# Supply_DAC.net
KiCad netlist of a schematic drawn in Altium Designer
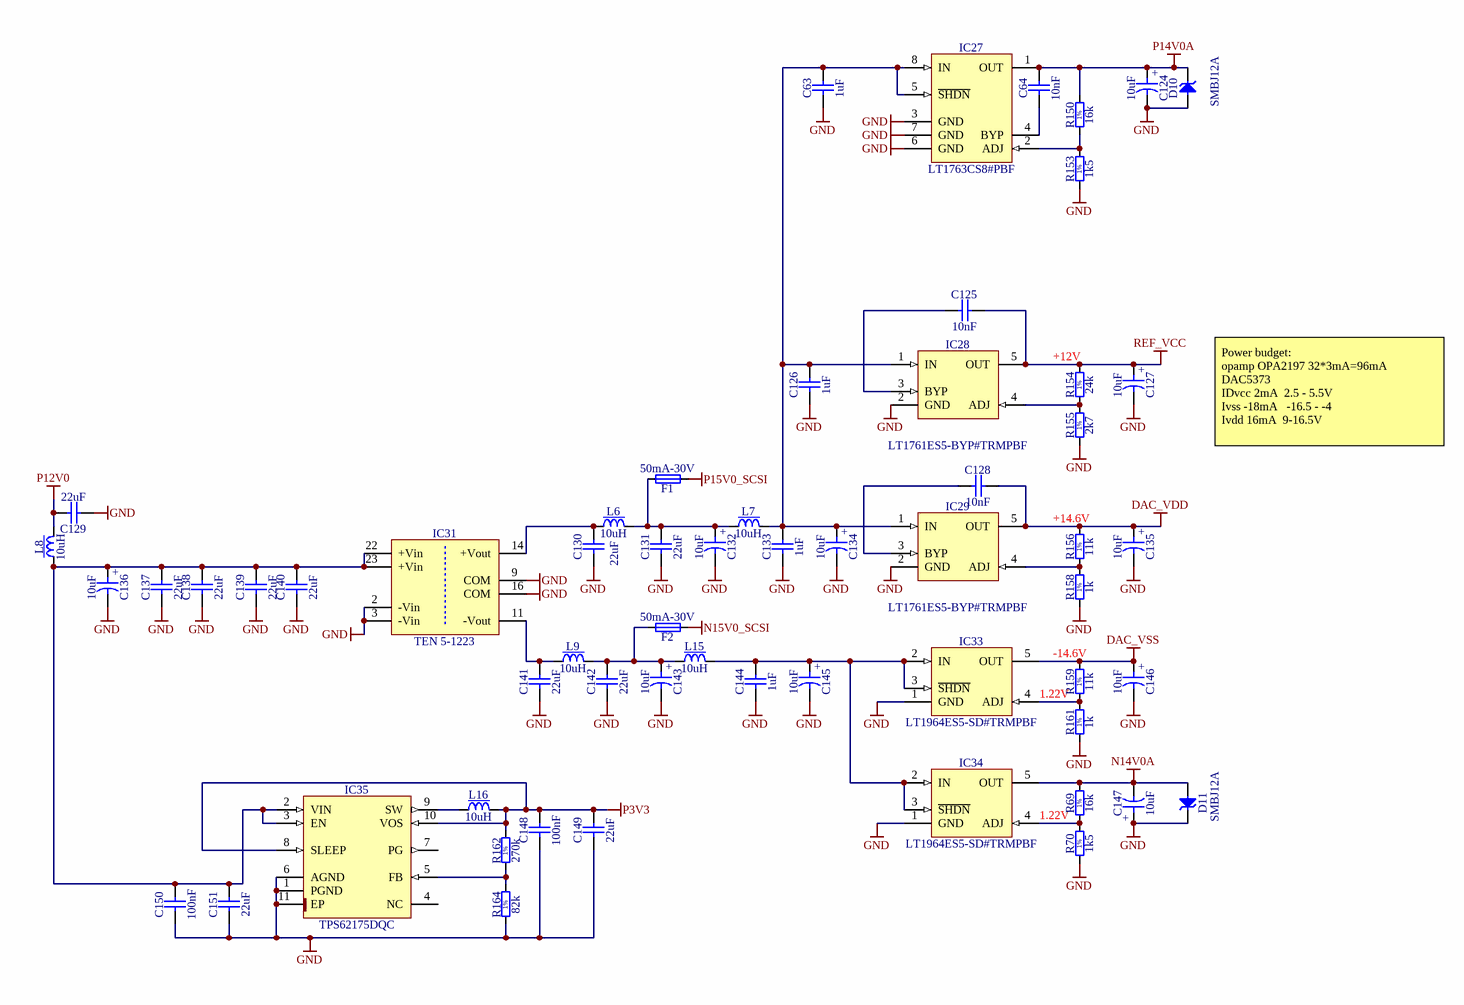
[diagram p0: Supply_DAC.SchDoc]

(export (version "E")
  (design (tool "Eeschema 10.0.6"))
  (components
    (comp (ref "C63")
      (value "1uF")
      (footprint "CAPC1608X87N")
      (description "Non-polarised capacitor")
      (fields
        (field (name "PART NUMBER") "CC0603_1UF_25V_10%_X7R")
        (field (name "VOLTAGE") "25V")
        (field (name "AUTHOR") "CERN DEM JLC")
      )
      (libsource (lib "Capacitors") (part "Capacitor - non polarized"))
    )
    (comp (ref "C64")
      (value "10nF")
      (footprint "CAPC1608X87N")
      (description "Non-polarised capacitor")
      (fields
        (field (name "PART NUMBER") "CC0603_10NF_50V_10%_X7R")
        (field (name "VOLTAGE") "50V")
        (field (name "AUTHOR") "CERN DEM JLC")
      )
      (libsource (lib "Capacitors") (part "Capacitor - non polarized"))
    )
    (comp (ref "C124")
      (value "10uF")
      (footprint "CAPMP3216X180N")
      (description "Polarised capacitor")
      (fields
        (field (name "PART NUMBER") "CTE3216-18_10UF_16V_20%_AVX_TCJ")
        (field (name "VOLTAGE") "16V")
        (field (name "AUTHOR") "CERN DEM JLC")
      )
      (libsource (lib "Capacitors") (part "Capacitor - polarized"))
    )
    (comp (ref "C125")
      (value "10nF")
      (footprint "CAPC1608X87N")
      (description "Non-polarised capacitor")
      (fields
        (field (name "PART NUMBER") "CC0603_10NF_50V_10%_X7R")
        (field (name "VOLTAGE") "50V")
        (field (name "AUTHOR") "CERN DEM JLC")
      )
      (libsource (lib "Capacitors") (part "Capacitor - non polarized"))
    )
    (comp (ref "C126")
      (value "1uF")
      (footprint "CAPC1608X87N")
      (description "Non-polarised capacitor")
      (fields
        (field (name "PART NUMBER") "CC0603_1UF_25V_10%_X7R")
        (field (name "VOLTAGE") "25V")
        (field (name "AUTHOR") "CERN DEM JLC")
      )
      (libsource (lib "Capacitors") (part "Capacitor - non polarized"))
    )
    (comp (ref "C127")
      (value "10uF")
      (footprint "CAPMP3216X180N")
      (description "Polarised capacitor")
      (fields
        (field (name "PART NUMBER") "CTE3216-18_10UF_16V_20%_AVX_TCJ")
        (field (name "VOLTAGE") "16V")
        (field (name "AUTHOR") "CERN DEM JLC")
      )
      (libsource (lib "Capacitors") (part "Capacitor - polarized"))
    )
    (comp (ref "C128")
      (value "10nF")
      (footprint "CAPC1608X87N")
      (description "Non-polarised capacitor")
      (fields
        (field (name "PART NUMBER") "CC0603_10NF_50V_10%_X7R")
        (field (name "VOLTAGE") "50V")
        (field (name "AUTHOR") "CERN DEM JLC")
      )
      (libsource (lib "Capacitors") (part "Capacitor - non polarized"))
    )
    (comp (ref "C129")
      (value "22uF")
      (footprint "CAPC2012X135N")
      (description "Non-polarised capacitor")
      (fields
        (field (name "PART NUMBER") "CC0805_22UF_16V_10%_X5R")
        (field (name "VOLTAGE") "16V")
        (field (name "AUTHOR") "CERN DEM JLC")
      )
      (libsource (lib "Capacitors") (part "Capacitor - non polarized"))
    )
    (comp (ref "C130")
      (value "22uF")
      (footprint "CAPC2012X135N")
      (description "Non-polarised capacitor")
      (fields
        (field (name "PART NUMBER") "CC0805_22UF_16V_10%_X5R")
        (field (name "VOLTAGE") "16V")
        (field (name "AUTHOR") "CERN DEM JLC")
      )
      (libsource (lib "Capacitors") (part "Capacitor - non polarized"))
    )
    (comp (ref "C131")
      (value "22uF")
      (footprint "CAPC2012X135N")
      (description "Non-polarised capacitor")
      (fields
        (field (name "PART NUMBER") "CC0805_22UF_16V_10%_X5R")
        (field (name "VOLTAGE") "16V")
        (field (name "AUTHOR") "CERN DEM JLC")
      )
      (libsource (lib "Capacitors") (part "Capacitor - non polarized"))
    )
    (comp (ref "C132")
      (value "10uF")
      (footprint "CAPMP3216X180N")
      (description "Polarised capacitor")
      (fields
        (field (name "PART NUMBER") "CTE3216-18_10UF_16V_20%_AVX_TCJ")
        (field (name "VOLTAGE") "16V")
        (field (name "AUTHOR") "CERN DEM JLC")
      )
      (libsource (lib "Capacitors") (part "Capacitor - polarized"))
    )
    (comp (ref "C133")
      (value "1uF")
      (footprint "CAPC1608X87N")
      (description "Non-polarised capacitor")
      (fields
        (field (name "PART NUMBER") "CC0603_1UF_25V_10%_X7R")
        (field (name "VOLTAGE") "25V")
        (field (name "AUTHOR") "CERN DEM JLC")
      )
      (libsource (lib "Capacitors") (part "Capacitor - non polarized"))
    )
    (comp (ref "C134")
      (value "10uF")
      (footprint "CAPMP3216X180N")
      (description "Polarised capacitor")
      (fields
        (field (name "PART NUMBER") "CTE3216-18_10UF_16V_20%_AVX_TCJ")
        (field (name "VOLTAGE") "16V")
        (field (name "AUTHOR") "CERN DEM JLC")
      )
      (libsource (lib "Capacitors") (part "Capacitor - polarized"))
    )
    (comp (ref "C135")
      (value "10uF")
      (footprint "CAPMP3216X180N")
      (description "Polarised capacitor")
      (fields
        (field (name "PART NUMBER") "CTE3216-18_10UF_16V_20%_AVX_TCJ")
        (field (name "VOLTAGE") "16V")
        (field (name "AUTHOR") "CERN DEM JLC")
      )
      (libsource (lib "Capacitors") (part "Capacitor - polarized"))
    )
    (comp (ref "C136")
      (value "10uF")
      (footprint "CAPMP3216X180N")
      (description "Polarised capacitor")
      (fields
        (field (name "PART NUMBER") "CTE3216-18_10UF_16V_20%_AVX_TCJ")
        (field (name "VOLTAGE") "16V")
        (field (name "AUTHOR") "CERN DEM JLC")
      )
      (libsource (lib "Capacitors") (part "Capacitor - polarized"))
    )
    (comp (ref "C137")
      (value "22uF")
      (footprint "CAPC2012X135N")
      (description "Non-polarised capacitor")
      (fields
        (field (name "PART NUMBER") "CC0805_22UF_16V_10%_X5R")
        (field (name "VOLTAGE") "16V")
        (field (name "AUTHOR") "CERN DEM JLC")
      )
      (libsource (lib "Capacitors") (part "Capacitor - non polarized"))
    )
    (comp (ref "C138")
      (value "22uF")
      (footprint "CAPC2012X135N")
      (description "Non-polarised capacitor")
      (fields
        (field (name "PART NUMBER") "CC0805_22UF_16V_10%_X5R")
        (field (name "VOLTAGE") "16V")
        (field (name "AUTHOR") "CERN DEM JLC")
      )
      (libsource (lib "Capacitors") (part "Capacitor - non polarized"))
    )
    (comp (ref "C139")
      (value "22uF")
      (footprint "CAPC2012X135N")
      (description "Non-polarised capacitor")
      (fields
        (field (name "PART NUMBER") "CC0805_22UF_16V_10%_X5R")
        (field (name "VOLTAGE") "16V")
        (field (name "AUTHOR") "CERN DEM JLC")
      )
      (libsource (lib "Capacitors") (part "Capacitor - non polarized"))
    )
    (comp (ref "C140")
      (value "22uF")
      (footprint "CAPC2012X135N")
      (description "Non-polarised capacitor")
      (fields
        (field (name "PART NUMBER") "CC0805_22UF_16V_10%_X5R")
        (field (name "VOLTAGE") "16V")
        (field (name "AUTHOR") "CERN DEM JLC")
      )
      (libsource (lib "Capacitors") (part "Capacitor - non polarized"))
    )
    (comp (ref "C141")
      (value "22uF")
      (footprint "CAPC2012X135N")
      (description "Non-polarised capacitor")
      (fields
        (field (name "PART NUMBER") "CC0805_22UF_16V_10%_X5R")
        (field (name "VOLTAGE") "16V")
        (field (name "AUTHOR") "CERN DEM JLC")
      )
      (libsource (lib "Capacitors") (part "Capacitor - non polarized"))
    )
    (comp (ref "C142")
      (value "22uF")
      (footprint "CAPC2012X135N")
      (description "Non-polarised capacitor")
      (fields
        (field (name "PART NUMBER") "CC0805_22UF_16V_10%_X5R")
        (field (name "VOLTAGE") "16V")
        (field (name "AUTHOR") "CERN DEM JLC")
      )
      (libsource (lib "Capacitors") (part "Capacitor - non polarized"))
    )
    (comp (ref "C143")
      (value "10uF")
      (footprint "CAPMP3216X180N")
      (description "Polarised capacitor")
      (fields
        (field (name "PART NUMBER") "CTE3216-18_10UF_16V_20%_AVX_TCJ")
        (field (name "VOLTAGE") "16V")
        (field (name "AUTHOR") "CERN DEM JLC")
      )
      (libsource (lib "Capacitors") (part "Capacitor - polarized"))
    )
    (comp (ref "C144")
      (value "1uF")
      (footprint "CAPC1608X87N")
      (description "Non-polarised capacitor")
      (fields
        (field (name "PART NUMBER") "CC0603_1UF_25V_10%_X7R")
        (field (name "VOLTAGE") "25V")
        (field (name "AUTHOR") "CERN DEM JLC")
      )
      (libsource (lib "Capacitors") (part "Capacitor - non polarized"))
    )
    (comp (ref "C145")
      (value "10uF")
      (footprint "CAPMP3216X180N")
      (description "Polarised capacitor")
      (fields
        (field (name "PART NUMBER") "CTE3216-18_10UF_16V_20%_AVX_TCJ")
        (field (name "VOLTAGE") "16V")
        (field (name "AUTHOR") "CERN DEM JLC")
      )
      (libsource (lib "Capacitors") (part "Capacitor - polarized"))
    )
    (comp (ref "C146")
      (value "10uF")
      (footprint "CAPMP3216X180N")
      (description "Polarised capacitor")
      (fields
        (field (name "PART NUMBER") "CTE3216-18_10UF_16V_20%_AVX_TCJ")
        (field (name "VOLTAGE") "16V")
        (field (name "AUTHOR") "CERN DEM JLC")
      )
      (libsource (lib "Capacitors") (part "Capacitor - polarized"))
    )
    (comp (ref "C147")
      (value "10uF")
      (footprint "CAPMP3216X180N")
      (description "Polarised capacitor")
      (fields
        (field (name "PART NUMBER") "CTE3216-18_10UF_16V_20%_AVX_TCJ")
        (field (name "VOLTAGE") "16V")
        (field (name "AUTHOR") "CERN DEM JLC")
      )
      (libsource (lib "Capacitors") (part "Capacitor - polarized"))
    )
    (comp (ref "C148")
      (value "100nF")
      (footprint "CAPC1005X55N")
      (description "Non-polarised capacitor")
      (fields
        (field (name "PART NUMBER") "CC0402_100NF_16V_10%_X5R")
        (field (name "VOLTAGE") "16V")
        (field (name "AUTHOR") "CERN DEM JLC")
      )
      (libsource (lib "Capacitors") (part "Capacitor - non polarized"))
    )
    (comp (ref "C149")
      (value "22uF")
      (footprint "CAPC2012X135N")
      (description "Non-polarised capacitor")
      (fields
        (field (name "PART NUMBER") "CC0805_22UF_16V_10%_X5R")
        (field (name "VOLTAGE") "16V")
        (field (name "AUTHOR") "CERN DEM JLC")
      )
      (libsource (lib "Capacitors") (part "Capacitor - non polarized"))
    )
    (comp (ref "C150")
      (value "100nF")
      (footprint "CAPC1005X55N")
      (description "Non-polarised capacitor")
      (fields
        (field (name "PART NUMBER") "CC0402_100NF_16V_10%_X5R")
        (field (name "VOLTAGE") "16V")
        (field (name "AUTHOR") "CERN DEM JLC")
      )
      (libsource (lib "Capacitors") (part "Capacitor - non polarized"))
    )
    (comp (ref "C151")
      (value "22uF")
      (footprint "CAPC2012X135N")
      (description "Non-polarised capacitor")
      (fields
        (field (name "PART NUMBER") "CC0805_22UF_16V_10%_X5R")
        (field (name "VOLTAGE") "16V")
        (field (name "AUTHOR") "CERN DEM JLC")
      )
      (libsource (lib "Capacitors") (part "Capacitor - non polarized"))
    )
    (comp (ref "D10")
      (value "SMBJ12A")
      (footprint "DIOM5336X265N")
      (description "Zener Diode")
      (fields
        (field (name "VOLTAGE") "12V")
        (field (name "POWER") "600W")
        (field (name "AUTHOR") "CERN DEM JLC")
      )
      (libsource (lib "ICs And Semiconductors") (part "Diode Zener"))
    )
    (comp (ref "D11")
      (value "SMBJ12A")
      (footprint "DIOM5336X265N")
      (description "Zener Diode")
      (fields
        (field (name "VOLTAGE") "12V")
        (field (name "POWER") "600W")
        (field (name "AUTHOR") "CERN DEM JLC")
      )
      (libsource (lib "ICs And Semiconductors") (part "Diode Zener"))
    )
    (comp (ref "F1")
      (value "50mA-30V")
      (footprint "FUSRC3226X85N")
      (description "Fuse")
      (fields
        (field (name "PART NUMBER") "FUSR1210_TYCO-MICROSMD005F")
        (field (name "MANUFACTURER") "TYCO ELECTRONICS")
        (field (name "AUTHOR") "CERN DEM JLC")
      )
      (libsource (lib "Eletro-mechanical") (part "Fuse"))
    )
    (comp (ref "F2")
      (value "50mA-30V")
      (footprint "FUSRC3226X85N")
      (description "Fuse")
      (fields
        (field (name "PART NUMBER") "FUSR1210_TYCO-MICROSMD005F")
        (field (name "MANUFACTURER") "TYCO ELECTRONICS")
        (field (name "AUTHOR") "CERN DEM JLC")
      )
      (libsource (lib "Eletro-mechanical") (part "Fuse"))
    )
    (comp (ref "IC27")
      (value "LT1763CS8#PBF")
      (footprint "SOIC127P600X175-8N")
      (description "1.22V to 20V 500mA, Low Noise, LDO Adjustable Micropower Regulator")
      (fields (field (name "MANUFACTURER") "LINEAR TECHNOLOGY") (field (name "AUTHOR") "CERN DEM JLC"))
      (libsource (lib "ICs And Semiconductors") (part "LT1763xS8"))
    )
    (comp (ref "IC28")
      (value "LT1761ES5-BYP#TRMPBF")
      (footprint "SOT95P280X100-5N")
      (description "100mA, Low Noise, LDO Micropower Adjustable Regulator in SOT-23")
      (fields (field (name "MANUFACTURER") "LINEAR TECHNOLOGY") (field (name "AUTHOR") "CERN DEM MR"))
      (libsource (lib "ICs And Semiconductors") (part "LT1761-BYP"))
    )
    (comp (ref "IC29")
      (value "LT1761ES5-BYP#TRMPBF")
      (footprint "SOT95P280X100-5N")
      (description "100mA, Low Noise, LDO Micropower Adjustable Regulator in SOT-23")
      (fields (field (name "MANUFACTURER") "LINEAR TECHNOLOGY") (field (name "AUTHOR") "CERN DEM MR"))
      (libsource (lib "ICs And Semiconductors") (part "LT1761-BYP"))
    )
    (comp (ref "IC31")
      (value "TEN 5-1223")
      (footprint "DCDC_TRACO_TEN5WI")
      (description "9-18V to ±15V, Iout (max) ±200mA, 6W DC-DC Converter")
      (fields (field (name "MANUFACTURER") "TRACO POWER") (field (name "AUTHOR") "GK"))
      (libsource (lib "LIBRARY_SCH") (part "DCDC_TRACO_TEN 5-1223"))
    )
    (comp (ref "IC33")
      (value "LT1964ES5-SD#TRMPBF")
      (footprint "SOT95P280X100-5N")
      (description "200mA, Low Noise, Low Dropout Negative Micropower Regulator")
      (fields (field (name "MANUFACTURER") "LINEAR TECHNOLOGY") (field (name "AUTHOR") "CERN DEM JLC"))
      (libsource (lib "ICs And Semiconductors") (part "LT1964-SD"))
    )
    (comp (ref "IC34")
      (value "LT1964ES5-SD#TRMPBF")
      (footprint "SOT95P280X100-5N")
      (description "200mA, Low Noise, Low Dropout Negative Micropower Regulator")
      (fields (field (name "MANUFACTURER") "LINEAR TECHNOLOGY") (field (name "AUTHOR") "CERN DEM JLC"))
      (libsource (lib "ICs And Semiconductors") (part "LT1964-SD"))
    )
    (comp (ref "IC35")
      (value "TPS62175DQC")
      (footprint "SON50P200X300X80-11N-R94X250")
      (description "4.75-28VDC to 1-6VDC, 500mA Step-Down Converter With Sleep Mode")
      (fields (field (name "MANUFACTURER") "TEXAS INSTRUMENTS") (field (name "AUTHOR") "CERN DEM JMW"))
      (libsource (lib "ICs And Semiconductors") (part "TPS62175"))
    )
    (comp (ref "L6")
      (value "10uH")
      (footprint "IND_MURATA-PS_8400")
      (description "Inductor With Core")
      (fields
        (field (name "PART NUMBER") "IND_10UH_10%_MURATA-PS_8400")
        (field (name "POWER") "950mA")
        (field (name "AUTHOR") "CERN DEM JLC")
      )
      (libsource (lib "Inductors & Transformers") (part "Inductor With Magnetic core"))
    )
    (comp (ref "L7")
      (value "10uH")
      (footprint "IND_MURATA-PS_8400")
      (description "Inductor With Core")
      (fields
        (field (name "PART NUMBER") "IND_10UH_10%_MURATA-PS_8400")
        (field (name "POWER") "950mA")
        (field (name "AUTHOR") "CERN DEM JLC")
      )
      (libsource (lib "Inductors & Transformers") (part "Inductor With Magnetic core"))
    )
    (comp (ref "L8")
      (value "10uH")
      (footprint "IND_MURATA-PS_8400")
      (description "Inductor With Core")
      (fields
        (field (name "PART NUMBER") "IND_10UH_10%_MURATA-PS_8400")
        (field (name "POWER") "950mA")
        (field (name "AUTHOR") "CERN DEM JLC")
      )
      (libsource (lib "") (part "Inductor With Magnetic core_1"))
    )
    (comp (ref "L9")
      (value "10uH")
      (footprint "IND_MURATA-PS_8400")
      (description "Inductor With Core")
      (fields
        (field (name "PART NUMBER") "IND_10UH_10%_MURATA-PS_8400")
        (field (name "POWER") "950mA")
        (field (name "AUTHOR") "CERN DEM JLC")
      )
      (libsource (lib "Inductors & Transformers") (part "Inductor With Magnetic core"))
    )
    (comp (ref "L15")
      (value "10uH")
      (footprint "IND_MURATA-PS_8400")
      (description "Inductor With Core")
      (fields
        (field (name "PART NUMBER") "IND_10UH_10%_MURATA-PS_8400")
        (field (name "POWER") "950mA")
        (field (name "AUTHOR") "CERN DEM JLC")
      )
      (libsource (lib "Inductors & Transformers") (part "Inductor With Magnetic core"))
    )
    (comp (ref "L16")
      (value "10uH")
      (footprint "IND_MURATA-PS_8400")
      (description "Inductor With Core")
      (fields
        (field (name "PART NUMBER") "IND_10UH_10%_MURATA-PS_8400")
        (field (name "POWER") "950mA")
        (field (name "AUTHOR") "CERN DEM JLC")
      )
      (libsource (lib "Inductors & Transformers") (part "Inductor With Magnetic core"))
    )
    (comp (ref "R69")
      (value "16k")
      (footprint "RESC1608X55N")
      (description "Resistor - 1%")
      (fields
        (field (name "PART NUMBER") "R0603_16K_1%_0.1W_100PPM")
        (field (name "POWER") "0.1W")
        (field (name "AUTHOR") "CERN DEM JLC")
      )
      (libsource (lib "Resistors") (part "Resistor - 1%"))
    )
    (comp (ref "R70")
      (value "1k5")
      (footprint "RESC1608X55N")
      (description "Resistor - 1%")
      (fields
        (field (name "PART NUMBER") "R0603_1K5_1%_0.1W_100PPM")
        (field (name "POWER") "0.1W")
        (field (name "AUTHOR") "CERN DEM JLC")
      )
      (libsource (lib "Resistors") (part "Resistor - 1%"))
    )
    (comp (ref "R150")
      (value "16k")
      (footprint "RESC1608X55N")
      (description "Resistor - 1%")
      (fields
        (field (name "PART NUMBER") "R0603_16K_1%_0.1W_100PPM")
        (field (name "POWER") "0.1W")
        (field (name "AUTHOR") "CERN DEM JLC")
      )
      (libsource (lib "Resistors") (part "Resistor - 1%"))
    )
    (comp (ref "R153")
      (value "1k5")
      (footprint "RESC1608X55N")
      (description "Resistor - 1%")
      (fields
        (field (name "PART NUMBER") "R0603_1K5_1%_0.1W_100PPM")
        (field (name "POWER") "0.1W")
        (field (name "AUTHOR") "CERN DEM JLC")
      )
      (libsource (lib "Resistors") (part "Resistor - 1%"))
    )
    (comp (ref "R154")
      (value "24k")
      (footprint "RESC1608X55N")
      (description "Resistor - 1%")
      (fields
        (field (name "PART NUMBER") "R0603_24K_1%_0.1W_100PPM")
        (field (name "POWER") "0.1W")
        (field (name "AUTHOR") "CERN DEM JLC")
      )
      (libsource (lib "Resistors") (part "Resistor - 1%"))
    )
    (comp (ref "R155")
      (value "2k7")
      (footprint "RESC1608X55N")
      (description "Resistor - 1%")
      (fields
        (field (name "PART NUMBER") "R0603_2K7_1%_0.1W_100PPM")
        (field (name "POWER") "0.1W")
        (field (name "AUTHOR") "CERN DEM JLC")
      )
      (libsource (lib "Resistors") (part "Resistor - 1%"))
    )
    (comp (ref "R156")
      (value "11k")
      (footprint "RESC1608X55N")
      (description "Resistor - 1%")
      (fields
        (field (name "PART NUMBER") "R0603_11K_1%_0.1W_100PPM")
        (field (name "POWER") "0.1W")
        (field (name "AUTHOR") "CERN DEM JLC")
      )
      (libsource (lib "Resistors") (part "Resistor - 1%"))
    )
    (comp (ref "R158")
      (value "1k")
      (footprint "RESC1608X55N")
      (description "Resistor - 1%")
      (fields
        (field (name "PART NUMBER") "R0603_1K_1%_0.1W_100PPM")
        (field (name "POWER") "0.1W")
        (field (name "AUTHOR") "CERN DEM JLC")
      )
      (libsource (lib "Resistors") (part "Resistor - 1%"))
    )
    (comp (ref "R159")
      (value "11k")
      (footprint "RESC1608X55N")
      (description "Resistor - 1%")
      (fields
        (field (name "PART NUMBER") "R0603_11K_1%_0.1W_100PPM")
        (field (name "POWER") "0.1W")
        (field (name "AUTHOR") "CERN DEM JLC")
      )
      (libsource (lib "Resistors") (part "Resistor - 1%"))
    )
    (comp (ref "R161")
      (value "1k")
      (footprint "RESC1608X55N")
      (description "Resistor - 1%")
      (fields
        (field (name "PART NUMBER") "R0603_1K_1%_0.1W_100PPM")
        (field (name "POWER") "0.1W")
        (field (name "AUTHOR") "CERN DEM JLC")
      )
      (libsource (lib "Resistors") (part "Resistor - 1%"))
    )
    (comp (ref "R162")
      (value "270k")
      (footprint "RESC1608X55N")
      (description "Resistor - 1%")
      (fields
        (field (name "PART NUMBER") "R0603_270K_1%_0.1W_100PPM")
        (field (name "POWER") "0.1W")
        (field (name "AUTHOR") "CERN DEM JLC")
      )
      (libsource (lib "Resistors") (part "Resistor - 1%"))
    )
    (comp (ref "R164")
      (value "82k")
      (footprint "RESC1608X55N")
      (description "Resistor - 1%")
      (fields
        (field (name "PART NUMBER") "R0603_82K_1%_0.1W_100PPM")
        (field (name "POWER") "0.1W")
        (field (name "AUTHOR") "CERN DEM JLC")
      )
      (libsource (lib "Resistors") (part "Resistor - 1%"))
    )
  )
  (nets
    (net (code "1") (name "DAC_VDD") (class "Default")
      (node (ref "C128") (pin "2") (pinfunction "2_2") (pintype "passive"))
      (node (ref "C135") (pin "1") (pinfunction "1_1") (pintype "passive"))
      (node (ref "IC29") (pin "5") (pinfunction "OUT_5") (pintype "power_in"))
      (node (ref "R156") (pin "2") (pinfunction "2_2") (pintype "passive"))
    )
    (net (code "2") (name "DAC_VSS") (class "Default")
      (node (ref "C146") (pin "1") (pinfunction "1_1") (pintype "passive"))
      (node (ref "IC33") (pin "5") (pinfunction "OUT_5") (pintype "power_in"))
      (node (ref "R159") (pin "2") (pinfunction "2_2") (pintype "passive"))
    )
    (net (code "3") (name "GND") (class "Default")
      (node (ref "C124") (pin "2") (pinfunction "2_2") (pintype "passive"))
      (node (ref "C126") (pin "1") (pinfunction "1_1") (pintype "passive"))
      (node (ref "C127") (pin "2") (pinfunction "2_2") (pintype "passive"))
      (node (ref "C129") (pin "1") (pinfunction "1_1") (pintype "passive"))
      (node (ref "C130") (pin "1") (pinfunction "1_1") (pintype "passive"))
      (node (ref "C131") (pin "1") (pinfunction "1_1") (pintype "passive"))
      (node (ref "C132") (pin "2") (pinfunction "2_2") (pintype "passive"))
      (node (ref "C133") (pin "1") (pinfunction "1_1") (pintype "passive"))
      (node (ref "C134") (pin "2") (pinfunction "2_2") (pintype "passive"))
      (node (ref "C135") (pin "2") (pinfunction "2_2") (pintype "passive"))
      (node (ref "C136") (pin "2") (pinfunction "2_2") (pintype "passive"))
      (node (ref "C137") (pin "1") (pinfunction "1_1") (pintype "passive"))
      (node (ref "C138") (pin "1") (pinfunction "1_1") (pintype "passive"))
      (node (ref "C139") (pin "1") (pinfunction "1_1") (pintype "passive"))
      (node (ref "C140") (pin "1") (pinfunction "1_1") (pintype "passive"))
      (node (ref "C141") (pin "1") (pinfunction "1_1") (pintype "passive"))
      (node (ref "C142") (pin "1") (pinfunction "1_1") (pintype "passive"))
      (node (ref "C143") (pin "2") (pinfunction "2_2") (pintype "passive"))
      (node (ref "C144") (pin "1") (pinfunction "1_1") (pintype "passive"))
      (node (ref "C145") (pin "2") (pinfunction "2_2") (pintype "passive"))
      (node (ref "C146") (pin "2") (pinfunction "2_2") (pintype "passive"))
      (node (ref "C147") (pin "1") (pinfunction "1_1") (pintype "passive"))
      (node (ref "C148") (pin "1") (pinfunction "1_1") (pintype "passive"))
      (node (ref "C149") (pin "1") (pinfunction "1_1") (pintype "passive"))
      (node (ref "C150") (pin "1") (pinfunction "1_1") (pintype "passive"))
      (node (ref "C151") (pin "1") (pinfunction "1_1") (pintype "passive"))
      (node (ref "C63") (pin "1") (pinfunction "1_1") (pintype "passive"))
      (node (ref "D10") (pin "2") (pinfunction "A_2") (pintype "passive"))
      (node (ref "D11") (pin "1") (pinfunction "C_1") (pintype "passive"))
      (node (ref "IC27") (pin "3") (pinfunction "GND_3") (pintype "power_in"))
      (node (ref "IC27") (pin "6") (pinfunction "GND_6") (pintype "power_in"))
      (node (ref "IC27") (pin "7") (pinfunction "GND_7") (pintype "power_in"))
      (node (ref "IC28") (pin "2") (pinfunction "GND_2") (pintype "power_in"))
      (node (ref "IC29") (pin "2") (pinfunction "GND_2") (pintype "power_in"))
      (node (ref "IC31") (pin "16") (pinfunction "COM_16") (pintype "power_in"))
      (node (ref "IC31") (pin "2") (pinfunction "-Vin_2") (pintype "power_in"))
      (node (ref "IC31") (pin "3") (pinfunction "-Vin_3") (pintype "power_in"))
      (node (ref "IC31") (pin "9") (pinfunction "COM_9") (pintype "power_in"))
      (node (ref "IC33") (pin "1") (pinfunction "GND_1") (pintype "power_in"))
      (node (ref "IC34") (pin "1") (pinfunction "GND_1") (pintype "power_in"))
      (node (ref "IC35") (pin "1") (pinfunction "PGND_1") (pintype "power_in"))
      (node (ref "IC35") (pin "11") (pinfunction "EP_11") (pintype "power_in"))
      (node (ref "IC35") (pin "6") (pinfunction "AGND_6") (pintype "power_in"))
      (node (ref "R153") (pin "1") (pinfunction "1_1") (pintype "passive"))
      (node (ref "R155") (pin "1") (pinfunction "1_1") (pintype "passive"))
      (node (ref "R158") (pin "1") (pinfunction "1_1") (pintype "passive"))
      (node (ref "R161") (pin "1") (pinfunction "1_1") (pintype "passive"))
      (node (ref "R164") (pin "1") (pinfunction "1_1") (pintype "passive"))
      (node (ref "R70") (pin "1") (pinfunction "1_1") (pintype "passive"))
    )
    (net (code "4") (name "N14V0A") (class "Default")
      (node (ref "C147") (pin "2") (pinfunction "2_2") (pintype "passive"))
      (node (ref "D11") (pin "2") (pinfunction "A_2") (pintype "passive"))
      (node (ref "IC34") (pin "5") (pinfunction "OUT_5") (pintype "power_in"))
      (node (ref "R69") (pin "2") (pinfunction "2_2") (pintype "passive"))
    )
    (net (code "5") (name "N15V0_SCSI") (class "Default")
      (node (ref "F2") (pin "1") (pinfunction "1_1") (pintype "passive"))
    )
    (net (code "6") (name "Net-(C131-Pad2)") (class "Default")
      (node (ref "C131") (pin "2") (pinfunction "2_2") (pintype "passive"))
      (node (ref "C132") (pin "1") (pinfunction "1_1") (pintype "passive"))
      (node (ref "F1") (pin "2") (pinfunction "2_2") (pintype "passive"))
      (node (ref "L6") (pin "2") (pinfunction "2_2") (pintype "passive"))
      (node (ref "L7") (pin "1") (pinfunction "1_1") (pintype "passive"))
    )
    (net (code "7") (name "Net-(C142-Pad2)") (class "Default")
      (node (ref "C142") (pin "2") (pinfunction "2_2") (pintype "passive"))
      (node (ref "C143") (pin "1") (pinfunction "1_1") (pintype "passive"))
      (node (ref "F2") (pin "2") (pinfunction "2_2") (pintype "passive"))
      (node (ref "L15") (pin "1") (pinfunction "1_1") (pintype "passive"))
      (node (ref "L9") (pin "2") (pinfunction "2_2") (pintype "passive"))
    )
    (net (code "8") (name "Net-(IC27-ADJ)") (class "Default")
      (node (ref "IC27") (pin "2") (pinfunction "ADJ_2") (pintype "input"))
      (node (ref "R150") (pin "1") (pinfunction "1_1") (pintype "passive"))
      (node (ref "R153") (pin "2") (pinfunction "2_2") (pintype "passive"))
    )
    (net (code "9") (name "Net-(IC27-BYP)") (class "Default")
      (node (ref "C64") (pin "1") (pinfunction "1_1") (pintype "passive"))
      (node (ref "IC27") (pin "4") (pinfunction "BYP_4") (pintype "passive"))
    )
    (net (code "10") (name "Net-(IC27-IN)") (class "Default")
      (node (ref "C126") (pin "2") (pinfunction "2_2") (pintype "passive"))
      (node (ref "C133") (pin "2") (pinfunction "2_2") (pintype "passive"))
      (node (ref "C134") (pin "1") (pinfunction "1_1") (pintype "passive"))
      (node (ref "C63") (pin "2") (pinfunction "2_2") (pintype "passive"))
      (node (ref "IC27") (pin "5") (pinfunction "~{SHDN}_5") (pintype "input"))
      (node (ref "IC27") (pin "8") (pinfunction "IN_8") (pintype "input"))
      (node (ref "IC28") (pin "1") (pinfunction "IN_1") (pintype "input"))
      (node (ref "IC29") (pin "1") (pinfunction "IN_1") (pintype "input"))
      (node (ref "L7") (pin "2") (pinfunction "2_2") (pintype "passive"))
    )
    (net (code "11") (name "Net-(IC28-ADJ)") (class "Default")
      (node (ref "IC28") (pin "4") (pinfunction "ADJ_4") (pintype "input"))
      (node (ref "R154") (pin "1") (pinfunction "1_1") (pintype "passive"))
      (node (ref "R155") (pin "2") (pinfunction "2_2") (pintype "passive"))
    )
    (net (code "12") (name "Net-(IC28-BYP)") (class "Default")
      (node (ref "C125") (pin "1") (pinfunction "1_1") (pintype "passive"))
      (node (ref "IC28") (pin "3") (pinfunction "BYP_3") (pintype "input"))
    )
    (net (code "13") (name "Net-(IC29-ADJ)") (class "Default")
      (node (ref "IC29") (pin "4") (pinfunction "ADJ_4") (pintype "input"))
      (node (ref "R156") (pin "1") (pinfunction "1_1") (pintype "passive"))
      (node (ref "R158") (pin "2") (pinfunction "2_2") (pintype "passive"))
    )
    (net (code "14") (name "Net-(IC29-BYP)") (class "Default")
      (node (ref "C128") (pin "1") (pinfunction "1_1") (pintype "passive"))
      (node (ref "IC29") (pin "3") (pinfunction "BYP_3") (pintype "input"))
    )
    (net (code "15") (name "Net-(IC31-+Vout)") (class "Default")
      (node (ref "C130") (pin "2") (pinfunction "2_2") (pintype "passive"))
      (node (ref "IC31") (pin "14") (pinfunction "+Vout_14") (pintype "power_in"))
      (node (ref "L6") (pin "1") (pinfunction "1_1") (pintype "passive"))
    )
    (net (code "16") (name "Net-(IC31--Vout)") (class "Default")
      (node (ref "C141") (pin "2") (pinfunction "2_2") (pintype "passive"))
      (node (ref "IC31") (pin "11") (pinfunction "-Vout_11") (pintype "power_in"))
      (node (ref "L9") (pin "1") (pinfunction "1_1") (pintype "passive"))
    )
    (net (code "17") (name "Net-(IC33-ADJ)") (class "Default")
      (node (ref "IC33") (pin "4") (pinfunction "ADJ_4") (pintype "input"))
      (node (ref "R159") (pin "1") (pinfunction "1_1") (pintype "passive"))
      (node (ref "R161") (pin "2") (pinfunction "2_2") (pintype "passive"))
    )
    (net (code "18") (name "Net-(IC33-IN)") (class "Default")
      (node (ref "C144") (pin "2") (pinfunction "2_2") (pintype "passive"))
      (node (ref "C145") (pin "1") (pinfunction "1_1") (pintype "passive"))
      (node (ref "IC33") (pin "2") (pinfunction "IN_2") (pintype "input"))
      (node (ref "IC33") (pin "3") (pinfunction "~{SHDN}_3") (pintype "input"))
      (node (ref "IC34") (pin "2") (pinfunction "IN_2") (pintype "input"))
      (node (ref "IC34") (pin "3") (pinfunction "~{SHDN}_3") (pintype "input"))
      (node (ref "L15") (pin "2") (pinfunction "2_2") (pintype "passive"))
    )
    (net (code "19") (name "Net-(IC34-ADJ)") (class "Default")
      (node (ref "IC34") (pin "4") (pinfunction "ADJ_4") (pintype "input"))
      (node (ref "R69") (pin "1") (pinfunction "1_1") (pintype "passive"))
      (node (ref "R70") (pin "2") (pinfunction "2_2") (pintype "passive"))
    )
    (net (code "20") (name "Net-(IC35-EN)") (class "Default")
      (node (ref "C136") (pin "1") (pinfunction "1_1") (pintype "passive"))
      (node (ref "C137") (pin "2") (pinfunction "2_2") (pintype "passive"))
      (node (ref "C138") (pin "2") (pinfunction "2_2") (pintype "passive"))
      (node (ref "C139") (pin "2") (pinfunction "2_2") (pintype "passive"))
      (node (ref "C140") (pin "2") (pinfunction "2_2") (pintype "passive"))
      (node (ref "C150") (pin "2") (pinfunction "2_2") (pintype "passive"))
      (node (ref "C151") (pin "2") (pinfunction "2_2") (pintype "passive"))
      (node (ref "IC31") (pin "22") (pinfunction "+Vin_22") (pintype "power_in"))
      (node (ref "IC31") (pin "23") (pinfunction "+Vin_23") (pintype "power_in"))
      (node (ref "IC35") (pin "2") (pinfunction "VIN_2") (pintype "input"))
      (node (ref "IC35") (pin "3") (pinfunction "EN_3") (pintype "input"))
      (node (ref "L8") (pin "1") (pinfunction "1_1") (pintype "passive"))
    )
    (net (code "21") (name "Net-(IC35-FB)") (class "Default")
      (node (ref "IC35") (pin "5") (pinfunction "FB_5") (pintype "input"))
      (node (ref "R162") (pin "1") (pinfunction "1_1") (pintype "passive"))
      (node (ref "R164") (pin "2") (pinfunction "2_2") (pintype "passive"))
    )
    (net (code "22") (name "Net-(IC35-SW)") (class "Default")
      (node (ref "IC35") (pin "9") (pinfunction "SW_9") (pintype "output"))
      (node (ref "L16") (pin "1") (pinfunction "1_1") (pintype "passive"))
    )
    (net (code "23") (name "P3V3") (class "Default")
      (node (ref "C148") (pin "2") (pinfunction "2_2") (pintype "passive"))
      (node (ref "C149") (pin "2") (pinfunction "2_2") (pintype "passive"))
      (node (ref "IC35") (pin "10") (pinfunction "VOS_10") (pintype "input"))
      (node (ref "IC35") (pin "8") (pinfunction "SLEEP_8") (pintype "input"))
      (node (ref "L16") (pin "2") (pinfunction "2_2") (pintype "passive"))
      (node (ref "R162") (pin "2") (pinfunction "2_2") (pintype "passive"))
    )
    (net (code "24") (name "P12V0") (class "Default")
      (node (ref "C129") (pin "2") (pinfunction "2_2") (pintype "passive"))
      (node (ref "L8") (pin "2") (pinfunction "2_2") (pintype "passive"))
    )
    (net (code "25") (name "P14V0A") (class "Default")
      (node (ref "C124") (pin "1") (pinfunction "1_1") (pintype "passive"))
      (node (ref "C64") (pin "2") (pinfunction "2_2") (pintype "passive"))
      (node (ref "D10") (pin "1") (pinfunction "C_1") (pintype "passive"))
      (node (ref "IC27") (pin "1") (pinfunction "OUT_1") (pintype "power_in"))
      (node (ref "R150") (pin "2") (pinfunction "2_2") (pintype "passive"))
    )
    (net (code "26") (name "P15V0_SCSI") (class "Default")
      (node (ref "F1") (pin "1") (pinfunction "1_1") (pintype "passive"))
    )
    (net (code "27") (name "REF_VCC") (class "Default")
      (node (ref "C125") (pin "2") (pinfunction "2_2") (pintype "passive"))
      (node (ref "C127") (pin "1") (pinfunction "1_1") (pintype "passive"))
      (node (ref "IC28") (pin "5") (pinfunction "OUT_5") (pintype "power_in"))
      (node (ref "R154") (pin "2") (pinfunction "2_2") (pintype "passive"))
    )
    (net (code "28") (name "unconnected-(IC35-NC-Pad4)") (class "Default")
      (node (ref "IC35") (pin "4") (pinfunction "NC_4") (pintype "passive"))
    )
    (net (code "29") (name "unconnected-(IC35-PG-Pad7)") (class "Default")
      (node (ref "IC35") (pin "7") (pinfunction "PG_7") (pintype "output"))
    )
  )
)
